# DDR3.net
KiCad netlist of a schematic drawn in Altium Designer
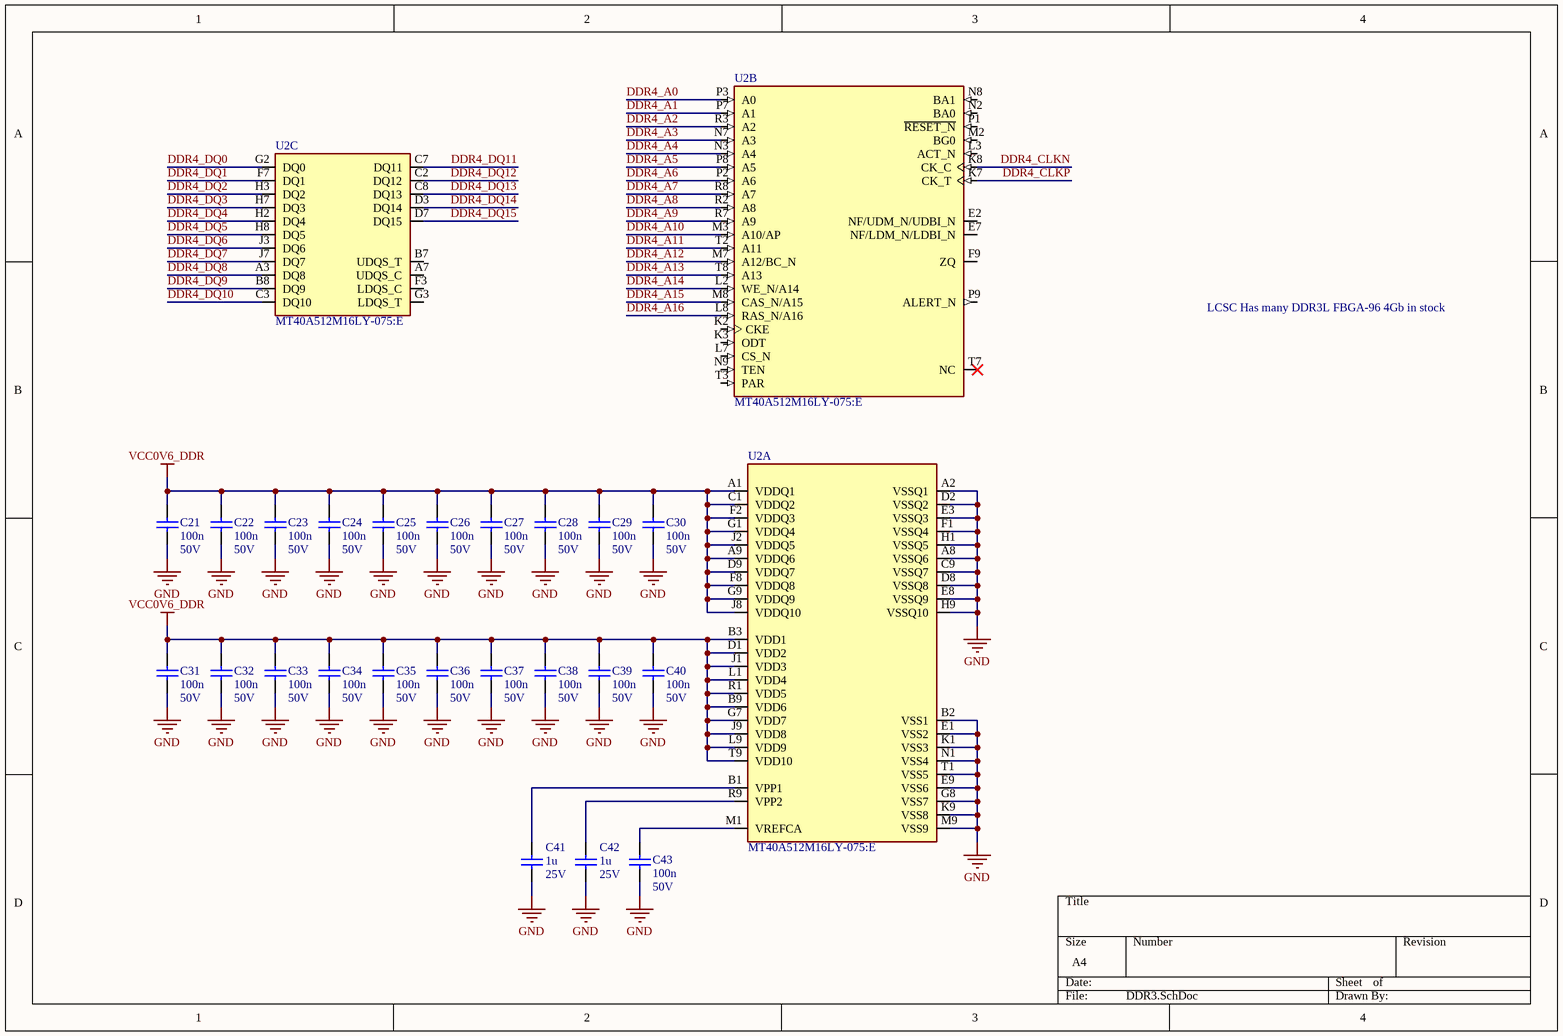
[diagram p0: DDR3.SchDoc]

(export (version "E")
  (design (tool "Eeschema 10.0.6"))
  (components
    (comp (ref "C21")
      (value "100n")
      (footprint "GRM155R71H104KE14D")
      (description "CAP 100N 50V X7R 0402")
      (fields (field (name "VOLTAGE") "50V") (field (name "Comment") "GRM155R71H104KE14D"))
      (libsource (lib "PersonalAltiumLibrary") (part "GRM155R71H104KE14D"))
    )
    (comp (ref "C22")
      (value "100n")
      (footprint "GRM155R71H104KE14D")
      (description "CAP 100N 50V X7R 0402")
      (fields (field (name "VOLTAGE") "50V") (field (name "Comment") "GRM155R71H104KE14D"))
      (libsource (lib "PersonalAltiumLibrary") (part "GRM155R71H104KE14D"))
    )
    (comp (ref "C23")
      (value "100n")
      (footprint "GRM155R71H104KE14D")
      (description "CAP 100N 50V X7R 0402")
      (fields (field (name "VOLTAGE") "50V") (field (name "Comment") "GRM155R71H104KE14D"))
      (libsource (lib "PersonalAltiumLibrary") (part "GRM155R71H104KE14D"))
    )
    (comp (ref "C24")
      (value "100n")
      (footprint "GRM155R71H104KE14D")
      (description "CAP 100N 50V X7R 0402")
      (fields (field (name "VOLTAGE") "50V") (field (name "Comment") "GRM155R71H104KE14D"))
      (libsource (lib "PersonalAltiumLibrary") (part "GRM155R71H104KE14D"))
    )
    (comp (ref "C25")
      (value "100n")
      (footprint "GRM155R71H104KE14D")
      (description "CAP 100N 50V X7R 0402")
      (fields (field (name "VOLTAGE") "50V") (field (name "Comment") "GRM155R71H104KE14D"))
      (libsource (lib "PersonalAltiumLibrary") (part "GRM155R71H104KE14D"))
    )
    (comp (ref "C26")
      (value "100n")
      (footprint "GRM155R71H104KE14D")
      (description "CAP 100N 50V X7R 0402")
      (fields (field (name "VOLTAGE") "50V") (field (name "Comment") "GRM155R71H104KE14D"))
      (libsource (lib "PersonalAltiumLibrary") (part "GRM155R71H104KE14D"))
    )
    (comp (ref "C27")
      (value "100n")
      (footprint "GRM155R71H104KE14D")
      (description "CAP 100N 50V X7R 0402")
      (fields (field (name "VOLTAGE") "50V") (field (name "Comment") "GRM155R71H104KE14D"))
      (libsource (lib "PersonalAltiumLibrary") (part "GRM155R71H104KE14D"))
    )
    (comp (ref "C28")
      (value "100n")
      (footprint "GRM155R71H104KE14D")
      (description "CAP 100N 50V X7R 0402")
      (fields (field (name "VOLTAGE") "50V") (field (name "Comment") "GRM155R71H104KE14D"))
      (libsource (lib "PersonalAltiumLibrary") (part "GRM155R71H104KE14D"))
    )
    (comp (ref "C29")
      (value "100n")
      (footprint "GRM155R71H104KE14D")
      (description "CAP 100N 50V X7R 0402")
      (fields (field (name "VOLTAGE") "50V") (field (name "Comment") "GRM155R71H104KE14D"))
      (libsource (lib "PersonalAltiumLibrary") (part "GRM155R71H104KE14D"))
    )
    (comp (ref "C30")
      (value "100n")
      (footprint "GRM155R71H104KE14D")
      (description "CAP 100N 50V X7R 0402")
      (fields (field (name "VOLTAGE") "50V") (field (name "Comment") "GRM155R71H104KE14D"))
      (libsource (lib "PersonalAltiumLibrary") (part "GRM155R71H104KE14D"))
    )
    (comp (ref "C31")
      (value "100n")
      (footprint "GRM155R71H104KE14D")
      (description "CAP 100N 50V X7R 0402")
      (fields (field (name "VOLTAGE") "50V") (field (name "Comment") "GRM155R71H104KE14D"))
      (libsource (lib "PersonalAltiumLibrary") (part "GRM155R71H104KE14D"))
    )
    (comp (ref "C32")
      (value "100n")
      (footprint "GRM155R71H104KE14D")
      (description "CAP 100N 50V X7R 0402")
      (fields (field (name "VOLTAGE") "50V") (field (name "Comment") "GRM155R71H104KE14D"))
      (libsource (lib "PersonalAltiumLibrary") (part "GRM155R71H104KE14D"))
    )
    (comp (ref "C33")
      (value "100n")
      (footprint "GRM155R71H104KE14D")
      (description "CAP 100N 50V X7R 0402")
      (fields (field (name "VOLTAGE") "50V") (field (name "Comment") "GRM155R71H104KE14D"))
      (libsource (lib "PersonalAltiumLibrary") (part "GRM155R71H104KE14D"))
    )
    (comp (ref "C34")
      (value "100n")
      (footprint "GRM155R71H104KE14D")
      (description "CAP 100N 50V X7R 0402")
      (fields (field (name "VOLTAGE") "50V") (field (name "Comment") "GRM155R71H104KE14D"))
      (libsource (lib "PersonalAltiumLibrary") (part "GRM155R71H104KE14D"))
    )
    (comp (ref "C35")
      (value "100n")
      (footprint "GRM155R71H104KE14D")
      (description "CAP 100N 50V X7R 0402")
      (fields (field (name "VOLTAGE") "50V") (field (name "Comment") "GRM155R71H104KE14D"))
      (libsource (lib "PersonalAltiumLibrary") (part "GRM155R71H104KE14D"))
    )
    (comp (ref "C36")
      (value "100n")
      (footprint "GRM155R71H104KE14D")
      (description "CAP 100N 50V X7R 0402")
      (fields (field (name "VOLTAGE") "50V") (field (name "Comment") "GRM155R71H104KE14D"))
      (libsource (lib "PersonalAltiumLibrary") (part "GRM155R71H104KE14D"))
    )
    (comp (ref "C37")
      (value "100n")
      (footprint "GRM155R71H104KE14D")
      (description "CAP 100N 50V X7R 0402")
      (fields (field (name "VOLTAGE") "50V") (field (name "Comment") "GRM155R71H104KE14D"))
      (libsource (lib "PersonalAltiumLibrary") (part "GRM155R71H104KE14D"))
    )
    (comp (ref "C38")
      (value "100n")
      (footprint "GRM155R71H104KE14D")
      (description "CAP 100N 50V X7R 0402")
      (fields (field (name "VOLTAGE") "50V") (field (name "Comment") "GRM155R71H104KE14D"))
      (libsource (lib "PersonalAltiumLibrary") (part "GRM155R71H104KE14D"))
    )
    (comp (ref "C39")
      (value "100n")
      (footprint "GRM155R71H104KE14D")
      (description "CAP 100N 50V X7R 0402")
      (fields (field (name "VOLTAGE") "50V") (field (name "Comment") "GRM155R71H104KE14D"))
      (libsource (lib "PersonalAltiumLibrary") (part "GRM155R71H104KE14D"))
    )
    (comp (ref "C40")
      (value "100n")
      (footprint "GRM155R71H104KE14D")
      (description "CAP 100N 50V X7R 0402")
      (fields (field (name "VOLTAGE") "50V") (field (name "Comment") "GRM155R71H104KE14D"))
      (libsource (lib "PersonalAltiumLibrary") (part "GRM155R71H104KE14D"))
    )
    (comp (ref "C41")
      (value "1u")
      (footprint "GRM155R61E105KA12D")
      (description "CAP 1U 25V X5R 0402")
      (fields (field (name "VOLTAGE") "25V") (field (name "Comment") "GRM155R61E105KA12D"))
      (libsource (lib "PersonalAltiumLibrary") (part "GRM155R61E105KA12D"))
    )
    (comp (ref "C42")
      (value "1u")
      (footprint "GRM155R61E105KA12D")
      (description "CAP 1U 25V X5R 0402")
      (fields (field (name "VOLTAGE") "25V") (field (name "Comment") "GRM155R61E105KA12D"))
      (libsource (lib "PersonalAltiumLibrary") (part "GRM155R61E105KA12D"))
    )
    (comp (ref "C43")
      (value "100n")
      (footprint "GRM155R71H104KE14D")
      (description "CAP 100N 50V X7R 0402")
      (fields (field (name "VOLTAGE") "50V") (field (name "Comment") "GRM155R71H104KE14D"))
      (libsource (lib "PersonalAltiumLibrary") (part "GRM155R71H104KE14D"))
    )
    (comp (ref "U2")
      (value "MT40A512M16LY-075:E")
      (description "SDRAM - DDR4 Memory IC 8Gb (512M x 16) Parallel 1.33 GHz 96-FBGA (7.5x13.5)")
      (fields (field (name "MF") "Micron Technology Inc."))
      (libsource (lib "PersonalAltiumLibrary") (part "MT40A512M16LY-075{colon}E"))
    )
  )
  (nets
    (net (code "1") (name "/DDR4_A0") (class "Default")
      (node (ref "U2") (pin "P3") (pinfunction "A0_P3") (pintype "input"))
    )
    (net (code "2") (name "/DDR4_A1") (class "Default")
      (node (ref "U2") (pin "P7") (pinfunction "A1_P7") (pintype "input"))
    )
    (net (code "3") (name "/DDR4_A2") (class "Default")
      (node (ref "U2") (pin "R3") (pinfunction "A2_R3") (pintype "input"))
    )
    (net (code "4") (name "/DDR4_A3") (class "Default")
      (node (ref "U2") (pin "N7") (pinfunction "A3_N7") (pintype "input"))
    )
    (net (code "5") (name "/DDR4_A4") (class "Default")
      (node (ref "U2") (pin "N3") (pinfunction "A4_N3") (pintype "input"))
    )
    (net (code "6") (name "/DDR4_A5") (class "Default")
      (node (ref "U2") (pin "P8") (pinfunction "A5_P8") (pintype "input"))
    )
    (net (code "7") (name "/DDR4_A6") (class "Default")
      (node (ref "U2") (pin "P2") (pinfunction "A6_P2") (pintype "input"))
    )
    (net (code "8") (name "/DDR4_A7") (class "Default")
      (node (ref "U2") (pin "R8") (pinfunction "A7_R8") (pintype "input"))
    )
    (net (code "9") (name "/DDR4_A8") (class "Default")
      (node (ref "U2") (pin "R2") (pinfunction "A8_R2") (pintype "input"))
    )
    (net (code "10") (name "/DDR4_A9") (class "Default")
      (node (ref "U2") (pin "R7") (pinfunction "A9_R7") (pintype "input"))
    )
    (net (code "11") (name "/DDR4_A10") (class "Default")
      (node (ref "U2") (pin "M3") (pinfunction "A10/AP_M3") (pintype "input"))
    )
    (net (code "12") (name "/DDR4_A11") (class "Default")
      (node (ref "U2") (pin "T2") (pinfunction "A11_T2") (pintype "input"))
    )
    (net (code "13") (name "/DDR4_A12") (class "Default")
      (node (ref "U2") (pin "M7") (pinfunction "A12/BC_N_M7") (pintype "input"))
    )
    (net (code "14") (name "/DDR4_A13") (class "Default")
      (node (ref "U2") (pin "T8") (pinfunction "A13_T8") (pintype "input"))
    )
    (net (code "15") (name "/DDR4_A14") (class "Default")
      (node (ref "U2") (pin "L2") (pinfunction "WE_N/A14_L2") (pintype "input"))
    )
    (net (code "16") (name "/DDR4_A15") (class "Default")
      (node (ref "U2") (pin "M8") (pinfunction "CAS_N/A15_M8") (pintype "input"))
    )
    (net (code "17") (name "/DDR4_A16") (class "Default")
      (node (ref "U2") (pin "L8") (pinfunction "RAS_N/A16_L8") (pintype "input"))
    )
    (net (code "18") (name "/DDR4_CLKN") (class "Default")
      (node (ref "U2") (pin "K8") (pinfunction "CK_C_K8") (pintype "input"))
    )
    (net (code "19") (name "/DDR4_CLKP") (class "Default")
      (node (ref "U2") (pin "K7") (pinfunction "CK_T_K7") (pintype "input"))
    )
    (net (code "20") (name "/DDR4_DQ0") (class "Default")
      (node (ref "U2") (pin "G2") (pinfunction "DQ0_G2") (pintype "bidirectional"))
    )
    (net (code "21") (name "/DDR4_DQ1") (class "Default")
      (node (ref "U2") (pin "F7") (pinfunction "DQ1_F7") (pintype "bidirectional"))
    )
    (net (code "22") (name "/DDR4_DQ2") (class "Default")
      (node (ref "U2") (pin "H3") (pinfunction "DQ2_H3") (pintype "bidirectional"))
    )
    (net (code "23") (name "/DDR4_DQ3") (class "Default")
      (node (ref "U2") (pin "H7") (pinfunction "DQ3_H7") (pintype "bidirectional"))
    )
    (net (code "24") (name "/DDR4_DQ4") (class "Default")
      (node (ref "U2") (pin "H2") (pinfunction "DQ4_H2") (pintype "bidirectional"))
    )
    (net (code "25") (name "/DDR4_DQ5") (class "Default")
      (node (ref "U2") (pin "H8") (pinfunction "DQ5_H8") (pintype "bidirectional"))
    )
    (net (code "26") (name "/DDR4_DQ6") (class "Default")
      (node (ref "U2") (pin "J3") (pinfunction "DQ6_J3") (pintype "bidirectional"))
    )
    (net (code "27") (name "/DDR4_DQ7") (class "Default")
      (node (ref "U2") (pin "J7") (pinfunction "DQ7_J7") (pintype "bidirectional"))
    )
    (net (code "28") (name "/DDR4_DQ8") (class "Default")
      (node (ref "U2") (pin "A3") (pinfunction "DQ8_A3") (pintype "bidirectional"))
    )
    (net (code "29") (name "/DDR4_DQ9") (class "Default")
      (node (ref "U2") (pin "B8") (pinfunction "DQ9_B8") (pintype "bidirectional"))
    )
    (net (code "30") (name "/DDR4_DQ10") (class "Default")
      (node (ref "U2") (pin "C3") (pinfunction "DQ10_C3") (pintype "bidirectional"))
    )
    (net (code "31") (name "/DDR4_DQ11") (class "Default")
      (node (ref "U2") (pin "C7") (pinfunction "DQ11_C7") (pintype "bidirectional"))
    )
    (net (code "32") (name "/DDR4_DQ12") (class "Default")
      (node (ref "U2") (pin "C2") (pinfunction "DQ12_C2") (pintype "bidirectional"))
    )
    (net (code "33") (name "/DDR4_DQ13") (class "Default")
      (node (ref "U2") (pin "C8") (pinfunction "DQ13_C8") (pintype "bidirectional"))
    )
    (net (code "34") (name "/DDR4_DQ14") (class "Default")
      (node (ref "U2") (pin "D3") (pinfunction "DQ14_D3") (pintype "bidirectional"))
    )
    (net (code "35") (name "/DDR4_DQ15") (class "Default")
      (node (ref "U2") (pin "D7") (pinfunction "DQ15_D7") (pintype "bidirectional"))
    )
    (net (code "36") (name "GND") (class "Default")
      (node (ref "C21") (pin "2") (pinfunction "2_2") (pintype "passive"))
      (node (ref "C22") (pin "2") (pinfunction "2_2") (pintype "passive"))
      (node (ref "C23") (pin "2") (pinfunction "2_2") (pintype "passive"))
      (node (ref "C24") (pin "2") (pinfunction "2_2") (pintype "passive"))
      (node (ref "C25") (pin "2") (pinfunction "2_2") (pintype "passive"))
      (node (ref "C26") (pin "2") (pinfunction "2_2") (pintype "passive"))
      (node (ref "C27") (pin "2") (pinfunction "2_2") (pintype "passive"))
      (node (ref "C28") (pin "2") (pinfunction "2_2") (pintype "passive"))
      (node (ref "C29") (pin "2") (pinfunction "2_2") (pintype "passive"))
      (node (ref "C30") (pin "2") (pinfunction "2_2") (pintype "passive"))
      (node (ref "C31") (pin "2") (pinfunction "2_2") (pintype "passive"))
      (node (ref "C32") (pin "2") (pinfunction "2_2") (pintype "passive"))
      (node (ref "C33") (pin "2") (pinfunction "2_2") (pintype "passive"))
      (node (ref "C34") (pin "2") (pinfunction "2_2") (pintype "passive"))
      (node (ref "C35") (pin "2") (pinfunction "2_2") (pintype "passive"))
      (node (ref "C36") (pin "2") (pinfunction "2_2") (pintype "passive"))
      (node (ref "C37") (pin "2") (pinfunction "2_2") (pintype "passive"))
      (node (ref "C38") (pin "2") (pinfunction "2_2") (pintype "passive"))
      (node (ref "C39") (pin "2") (pinfunction "2_2") (pintype "passive"))
      (node (ref "C40") (pin "2") (pinfunction "2_2") (pintype "passive"))
      (node (ref "C41") (pin "2") (pinfunction "2_2") (pintype "passive"))
      (node (ref "C42") (pin "2") (pinfunction "2_2") (pintype "passive"))
      (node (ref "C43") (pin "2") (pinfunction "2_2") (pintype "passive"))
      (node (ref "U2") (pin "A2") (pinfunction "VSSQ1_A2") (pintype "power_in"))
      (node (ref "U2") (pin "A8") (pinfunction "VSSQ6_A8") (pintype "power_in"))
      (node (ref "U2") (pin "B2") (pinfunction "VSS1_B2") (pintype "power_in"))
      (node (ref "U2") (pin "C9") (pinfunction "VSSQ7_C9") (pintype "power_in"))
      (node (ref "U2") (pin "D2") (pinfunction "VSSQ2_D2") (pintype "power_in"))
      (node (ref "U2") (pin "D8") (pinfunction "VSSQ8_D8") (pintype "power_in"))
      (node (ref "U2") (pin "E1") (pinfunction "VSS2_E1") (pintype "power_in"))
      (node (ref "U2") (pin "E3") (pinfunction "VSSQ3_E3") (pintype "power_in"))
      (node (ref "U2") (pin "E8") (pinfunction "VSSQ9_E8") (pintype "power_in"))
      (node (ref "U2") (pin "E9") (pinfunction "VSS6_E9") (pintype "power_in"))
      (node (ref "U2") (pin "F1") (pinfunction "VSSQ4_F1") (pintype "power_in"))
      (node (ref "U2") (pin "G8") (pinfunction "VSS7_G8") (pintype "power_in"))
      (node (ref "U2") (pin "H1") (pinfunction "VSSQ5_H1") (pintype "power_in"))
      (node (ref "U2") (pin "H9") (pinfunction "VSSQ10_H9") (pintype "power_in"))
      (node (ref "U2") (pin "K1") (pinfunction "VSS3_K1") (pintype "power_in"))
      (node (ref "U2") (pin "K9") (pinfunction "VSS8_K9") (pintype "power_in"))
      (node (ref "U2") (pin "M9") (pinfunction "VSS9_M9") (pintype "power_in"))
      (node (ref "U2") (pin "N1") (pinfunction "VSS4_N1") (pintype "power_in"))
      (node (ref "U2") (pin "T1") (pinfunction "VSS5_T1") (pintype "power_in"))
    )
    (net (code "37") (name "Net-(U2A-VPP1)") (class "Default")
      (node (ref "C41") (pin "1") (pinfunction "1_1") (pintype "passive"))
      (node (ref "U2") (pin "B1") (pinfunction "VPP1_B1") (pintype "power_in"))
    )
    (net (code "38") (name "Net-(U2A-VPP2)") (class "Default")
      (node (ref "C42") (pin "1") (pinfunction "1_1") (pintype "passive"))
      (node (ref "U2") (pin "R9") (pinfunction "VPP2_R9") (pintype "power_in"))
    )
    (net (code "39") (name "Net-(U2A-VREFCA)") (class "Default")
      (node (ref "C43") (pin "1") (pinfunction "1_1") (pintype "passive"))
      (node (ref "U2") (pin "M1") (pinfunction "VREFCA_M1") (pintype "power_in"))
    )
    (net (code "40") (name "VCC0V6_DDR") (class "Default")
      (node (ref "C21") (pin "1") (pinfunction "1_1") (pintype "passive"))
      (node (ref "C22") (pin "1") (pinfunction "1_1") (pintype "passive"))
      (node (ref "C23") (pin "1") (pinfunction "1_1") (pintype "passive"))
      (node (ref "C24") (pin "1") (pinfunction "1_1") (pintype "passive"))
      (node (ref "C25") (pin "1") (pinfunction "1_1") (pintype "passive"))
      (node (ref "C26") (pin "1") (pinfunction "1_1") (pintype "passive"))
      (node (ref "C27") (pin "1") (pinfunction "1_1") (pintype "passive"))
      (node (ref "C28") (pin "1") (pinfunction "1_1") (pintype "passive"))
      (node (ref "C29") (pin "1") (pinfunction "1_1") (pintype "passive"))
      (node (ref "C30") (pin "1") (pinfunction "1_1") (pintype "passive"))
      (node (ref "C31") (pin "1") (pinfunction "1_1") (pintype "passive"))
      (node (ref "C32") (pin "1") (pinfunction "1_1") (pintype "passive"))
      (node (ref "C33") (pin "1") (pinfunction "1_1") (pintype "passive"))
      (node (ref "C34") (pin "1") (pinfunction "1_1") (pintype "passive"))
      (node (ref "C35") (pin "1") (pinfunction "1_1") (pintype "passive"))
      (node (ref "C36") (pin "1") (pinfunction "1_1") (pintype "passive"))
      (node (ref "C37") (pin "1") (pinfunction "1_1") (pintype "passive"))
      (node (ref "C38") (pin "1") (pinfunction "1_1") (pintype "passive"))
      (node (ref "C39") (pin "1") (pinfunction "1_1") (pintype "passive"))
      (node (ref "C40") (pin "1") (pinfunction "1_1") (pintype "passive"))
      (node (ref "U2") (pin "A1") (pinfunction "VDDQ1_A1") (pintype "power_in"))
      (node (ref "U2") (pin "A9") (pinfunction "VDDQ6_A9") (pintype "power_in"))
      (node (ref "U2") (pin "B3") (pinfunction "VDD1_B3") (pintype "power_in"))
      (node (ref "U2") (pin "B9") (pinfunction "VDD6_B9") (pintype "power_in"))
      (node (ref "U2") (pin "C1") (pinfunction "VDDQ2_C1") (pintype "power_in"))
      (node (ref "U2") (pin "D1") (pinfunction "VDD2_D1") (pintype "power_in"))
      (node (ref "U2") (pin "D9") (pinfunction "VDDQ7_D9") (pintype "power_in"))
      (node (ref "U2") (pin "F2") (pinfunction "VDDQ3_F2") (pintype "power_in"))
      (node (ref "U2") (pin "F8") (pinfunction "VDDQ8_F8") (pintype "power_in"))
      (node (ref "U2") (pin "G1") (pinfunction "VDDQ4_G1") (pintype "power_in"))
      (node (ref "U2") (pin "G7") (pinfunction "VDD7_G7") (pintype "power_in"))
      (node (ref "U2") (pin "G9") (pinfunction "VDDQ9_G9") (pintype "power_in"))
      (node (ref "U2") (pin "J1") (pinfunction "VDD3_J1") (pintype "power_in"))
      (node (ref "U2") (pin "J2") (pinfunction "VDDQ5_J2") (pintype "power_in"))
      (node (ref "U2") (pin "J8") (pinfunction "VDDQ10_J8") (pintype "power_in"))
      (node (ref "U2") (pin "J9") (pinfunction "VDD8_J9") (pintype "power_in"))
      (node (ref "U2") (pin "L1") (pinfunction "VDD4_L1") (pintype "power_in"))
      (node (ref "U2") (pin "L9") (pinfunction "VDD9_L9") (pintype "power_in"))
      (node (ref "U2") (pin "R1") (pinfunction "VDD5_R1") (pintype "power_in"))
      (node (ref "U2") (pin "T9") (pinfunction "VDD10_T9") (pintype "power_in"))
    )
    (net (code "41") (name "unconnected-(U2B-ACT_N-PadL3)") (class "Default")
      (node (ref "U2") (pin "L3") (pinfunction "ACT_N_L3") (pintype "input"))
    )
    (net (code "42") (name "unconnected-(U2B-ALERT_N-PadP9)") (class "Default")
      (node (ref "U2") (pin "P9") (pinfunction "ALERT_N_P9") (pintype "output"))
    )
    (net (code "43") (name "unconnected-(U2B-BA0-PadN2)") (class "Default")
      (node (ref "U2") (pin "N2") (pinfunction "BA0_N2") (pintype "input"))
    )
    (net (code "44") (name "unconnected-(U2B-BA1-PadN8)") (class "Default")
      (node (ref "U2") (pin "N8") (pinfunction "BA1_N8") (pintype "input"))
    )
    (net (code "45") (name "unconnected-(U2B-BG0-PadM2)") (class "Default")
      (node (ref "U2") (pin "M2") (pinfunction "BG0_M2") (pintype "input"))
    )
    (net (code "46") (name "unconnected-(U2B-CKE-PadK2)") (class "Default")
      (node (ref "U2") (pin "K2") (pinfunction "CKE_K2") (pintype "input"))
    )
    (net (code "47") (name "unconnected-(U2B-CS_N-PadL7)") (class "Default")
      (node (ref "U2") (pin "L7") (pinfunction "CS_N_L7") (pintype "input"))
    )
    (net (code "48") (name "unconnected-(U2B-NC-PadT7)") (class "Default")
      (node (ref "U2") (pin "T7") (pinfunction "NC_T7") (pintype "passive+no_connect"))
    )
    (net (code "49") (name "unconnected-(U2B-NF{slash}LDM_N{slash}LDBI_N-PadE7)") (class "Default")
      (node (ref "U2") (pin "E7") (pinfunction "NF/LDM_N/LDBI_N_E7") (pintype "bidirectional"))
    )
    (net (code "50") (name "unconnected-(U2B-NF{slash}UDM_N{slash}UDBI_N-PadE2)") (class "Default")
      (node (ref "U2") (pin "E2") (pinfunction "NF/UDM_N/UDBI_N_E2") (pintype "bidirectional"))
    )
    (net (code "51") (name "unconnected-(U2B-ODT-PadK3)") (class "Default")
      (node (ref "U2") (pin "K3") (pinfunction "ODT_K3") (pintype "input"))
    )
    (net (code "52") (name "unconnected-(U2B-PAR-PadT3)") (class "Default")
      (node (ref "U2") (pin "T3") (pinfunction "PAR_T3") (pintype "input"))
    )
    (net (code "53") (name "unconnected-(U2B-TEN-PadN9)") (class "Default")
      (node (ref "U2") (pin "N9") (pinfunction "TEN_N9") (pintype "input"))
    )
    (net (code "54") (name "unconnected-(U2B-ZQ-PadF9)") (class "Default")
      (node (ref "U2") (pin "F9") (pinfunction "ZQ_F9") (pintype "passive"))
    )
    (net (code "55") (name "unconnected-(U2B-~{RESET_N}-PadP1)") (class "Default")
      (node (ref "U2") (pin "P1") (pinfunction "~{RESET_N}_P1") (pintype "input"))
    )
    (net (code "56") (name "unconnected-(U2C-LDQS_C-PadF3)") (class "Default")
      (node (ref "U2") (pin "F3") (pinfunction "LDQS_C_F3") (pintype "bidirectional"))
    )
    (net (code "57") (name "unconnected-(U2C-LDQS_T-PadG3)") (class "Default")
      (node (ref "U2") (pin "G3") (pinfunction "LDQS_T_G3") (pintype "bidirectional"))
    )
    (net (code "58") (name "unconnected-(U2C-UDQS_C-PadA7)") (class "Default")
      (node (ref "U2") (pin "A7") (pinfunction "UDQS_C_A7") (pintype "bidirectional"))
    )
    (net (code "59") (name "unconnected-(U2C-UDQS_T-PadB7)") (class "Default")
      (node (ref "U2") (pin "B7") (pinfunction "UDQS_T_B7") (pintype "bidirectional"))
    )
  )
)
